# sch_puertosx4.net
KiCad netlist of a schematic drawn in EAGLE
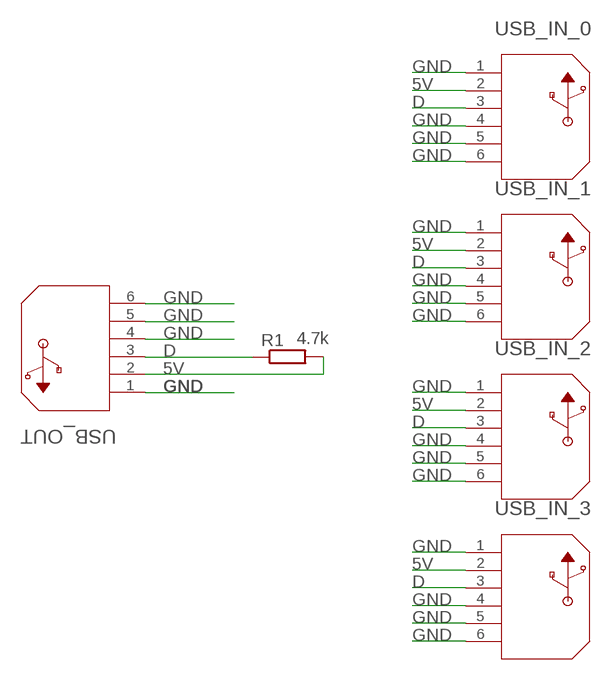
[diagram p0: schematic, sheet 1]

(export (version "E")
  (design (tool "Eeschema 10.0.6"))
  (components
    (comp (ref "R1")
      (value "4.7k")
      (footprint "eagle-import:0309_10")
      (libsource (lib "eagle-import") (part "R-EU_0309/10"))
    )
    (comp (ref "USB_IN_0")
      (value "292303-3")
      (footprint "eagle-import:CONN4_292303_TEC")
      (fields (field (name "COPYRIGHT") "Copyright (C) 2016 Accelerated Designs. All rights reserved"))
      (libsource (lib "eagle-import") (part "292303-3"))
    )
    (comp (ref "USB_IN_1")
      (value "292303-3")
      (footprint "eagle-import:CONN4_292303_TEC")
      (fields (field (name "COPYRIGHT") "Copyright (C) 2016 Accelerated Designs. All rights reserved"))
      (libsource (lib "eagle-import") (part "292303-3"))
    )
    (comp (ref "USB_IN_2")
      (value "292303-3")
      (footprint "eagle-import:CONN4_292303_TEC")
      (fields (field (name "COPYRIGHT") "Copyright (C) 2016 Accelerated Designs. All rights reserved"))
      (libsource (lib "eagle-import") (part "292303-3"))
    )
    (comp (ref "USB_IN_3")
      (value "292303-3")
      (footprint "eagle-import:CONN4_292303_TEC")
      (fields (field (name "COPYRIGHT") "Copyright (C) 2016 Accelerated Designs. All rights reserved"))
      (libsource (lib "eagle-import") (part "292303-3"))
    )
    (comp (ref "USB_OUT")
      (value "292303-3")
      (footprint "eagle-import:CONN4_292303_TEC")
      (fields (field (name "COPYRIGHT") "Copyright (C) 2016 Accelerated Designs. All rights reserved"))
      (libsource (lib "eagle-import") (part "292303-3"))
    )
  )
  (nets
    (net (code "1") (name "/5V") (class "Default")
      (node (ref "R1") (pin "2") (pinfunction "2_2") (pintype "passive"))
      (node (ref "USB_IN_0") (pin "2") (pinfunction "2_2") (pintype "passive"))
      (node (ref "USB_IN_1") (pin "2") (pinfunction "2_2") (pintype "passive"))
      (node (ref "USB_IN_2") (pin "2") (pinfunction "2_2") (pintype "passive"))
      (node (ref "USB_IN_3") (pin "2") (pinfunction "2_2") (pintype "passive"))
      (node (ref "USB_OUT") (pin "2") (pinfunction "2_2") (pintype "passive"))
    )
    (net (code "2") (name "/D") (class "Default")
      (node (ref "R1") (pin "1") (pinfunction "1_1") (pintype "passive"))
      (node (ref "USB_IN_0") (pin "3") (pinfunction "3_3") (pintype "passive"))
      (node (ref "USB_IN_1") (pin "3") (pinfunction "3_3") (pintype "passive"))
      (node (ref "USB_IN_2") (pin "3") (pinfunction "3_3") (pintype "passive"))
      (node (ref "USB_IN_3") (pin "3") (pinfunction "3_3") (pintype "passive"))
      (node (ref "USB_OUT") (pin "3") (pinfunction "3_3") (pintype "passive"))
    )
    (net (code "3") (name "/GND") (class "Default")
      (node (ref "USB_IN_0") (pin "1") (pinfunction "1_1") (pintype "passive"))
      (node (ref "USB_IN_0") (pin "4") (pinfunction "4_4") (pintype "passive"))
      (node (ref "USB_IN_0") (pin "5") (pinfunction "5_5") (pintype "passive"))
      (node (ref "USB_IN_0") (pin "6") (pinfunction "6_6") (pintype "passive"))
      (node (ref "USB_IN_1") (pin "1") (pinfunction "1_1") (pintype "passive"))
      (node (ref "USB_IN_1") (pin "4") (pinfunction "4_4") (pintype "passive"))
      (node (ref "USB_IN_1") (pin "5") (pinfunction "5_5") (pintype "passive"))
      (node (ref "USB_IN_1") (pin "6") (pinfunction "6_6") (pintype "passive"))
      (node (ref "USB_IN_2") (pin "1") (pinfunction "1_1") (pintype "passive"))
      (node (ref "USB_IN_2") (pin "4") (pinfunction "4_4") (pintype "passive"))
      (node (ref "USB_IN_2") (pin "5") (pinfunction "5_5") (pintype "passive"))
      (node (ref "USB_IN_2") (pin "6") (pinfunction "6_6") (pintype "passive"))
      (node (ref "USB_IN_3") (pin "1") (pinfunction "1_1") (pintype "passive"))
      (node (ref "USB_IN_3") (pin "4") (pinfunction "4_4") (pintype "passive"))
      (node (ref "USB_IN_3") (pin "5") (pinfunction "5_5") (pintype "passive"))
      (node (ref "USB_IN_3") (pin "6") (pinfunction "6_6") (pintype "passive"))
      (node (ref "USB_OUT") (pin "1") (pinfunction "1_1") (pintype "passive"))
      (node (ref "USB_OUT") (pin "4") (pinfunction "4_4") (pintype "passive"))
      (node (ref "USB_OUT") (pin "5") (pinfunction "5_5") (pintype "passive"))
      (node (ref "USB_OUT") (pin "6") (pinfunction "6_6") (pintype "passive"))
    )
  )
)
